# Power.net
KiCad netlist of a schematic drawn in Altium Designer
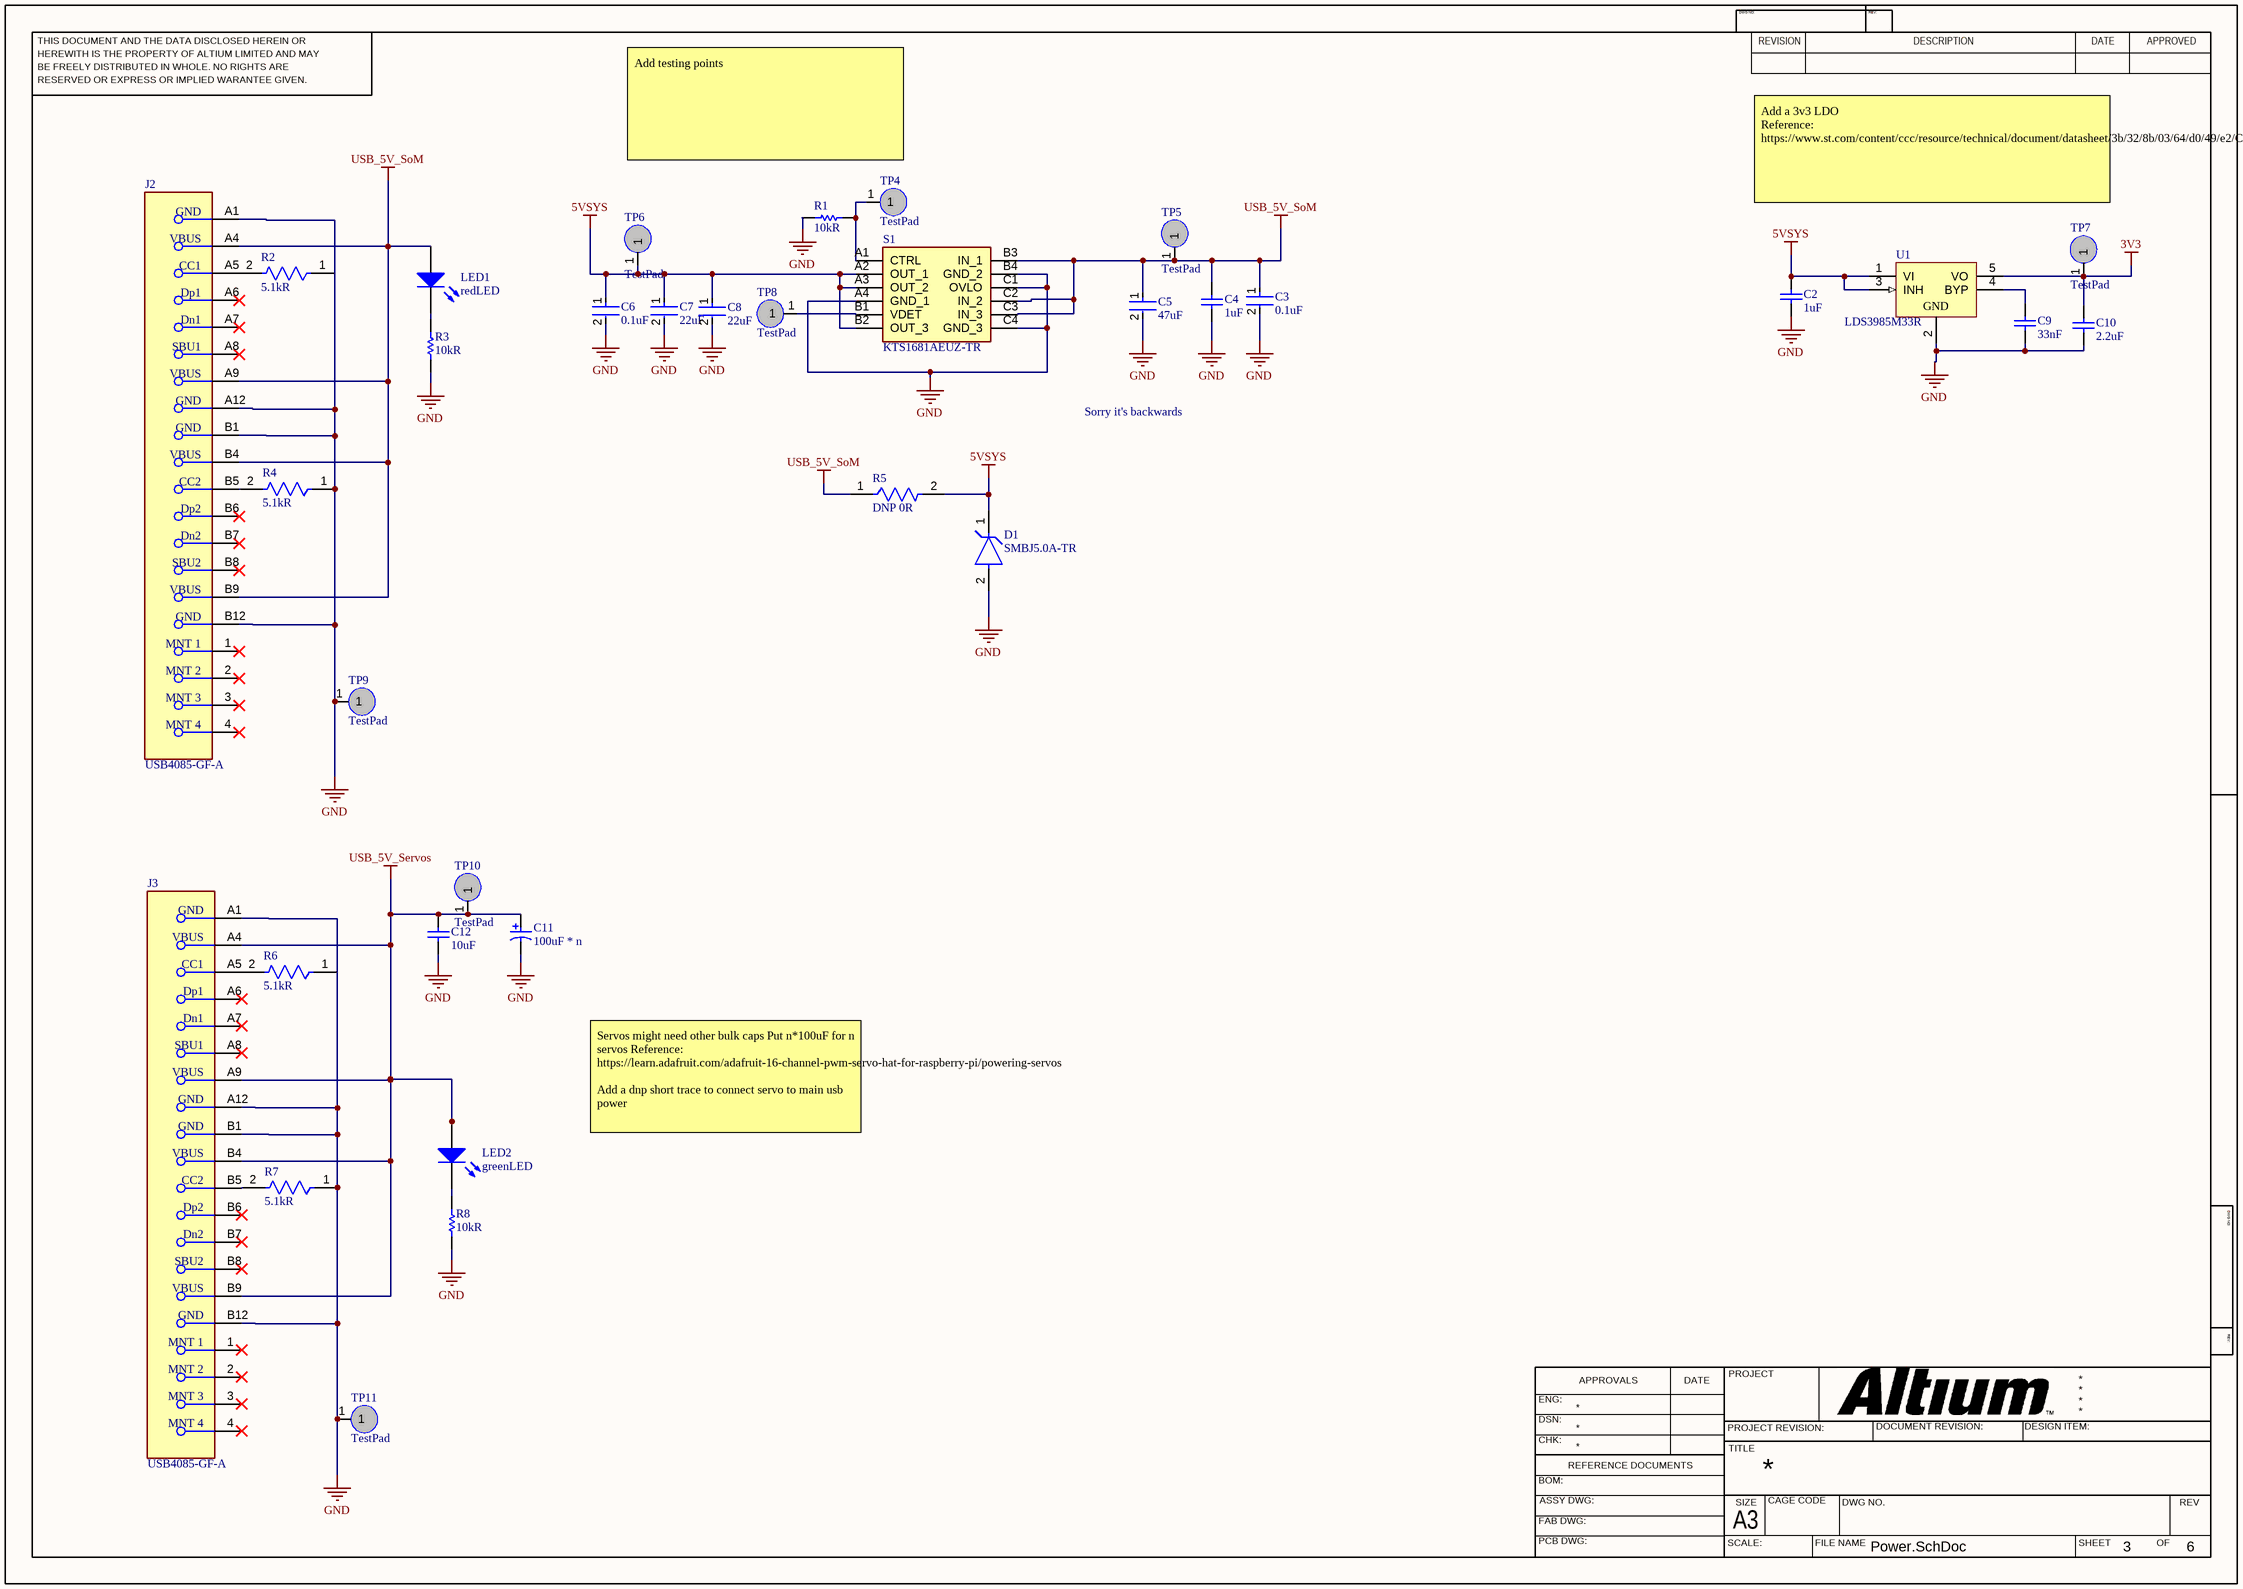
[diagram p0: Power.SchDoc]

(export (version "E")
  (design (tool "Eeschema 10.0.6"))
  (components
    (comp (ref "C2")
      (value "1uF")
      (footprint "CAPC2013X145X50LL20T25")
      (description "C0805C105K4PACTU")
      (fields (field (name "MANUFACTURER") "Kemet"))
      (libsource (lib "Altium Content Vault") (part "CAP"))
    )
    (comp (ref "C3")
      (value "0.1uF")
      (footprint "FP-C0603-CJ-MFG")
      (description "C0603X104K5RACTU CAP CER 0.1UF 50V X7R 0603")
      (fields (field (name "MANUFACTURER PART NUMBER") "C0603X104K5RACTU") (field (name "VOLTAGE") "50V"))
      (libsource (lib "Altium Content Vault") (part "11868f565c42a9108669ba33697ecf6"))
    )
    (comp (ref "C4")
      (value "1uF")
      (footprint "CAPC2013X145X50LL20T25")
      (description "C0805C105K4PACTU")
      (fields (field (name "MANUFACTURER") "Kemet"))
      (libsource (lib "Altium Content Vault") (part "CAP"))
    )
    (comp (ref "C5")
      (value "47uF")
      (footprint "FP-GRM31C-0_2-e0_3_0_8-IPC_C")
      (fields (field (name "TOLERANCE") "20%") (field (name "VOLTAGE") "6.3V"))
      (libsource (lib "Altium Content Vault") (part "02cd4be3c70576c341d710602a673aa"))
    )
    (comp (ref "C6")
      (value "0.1uF")
      (footprint "FP-C0603-CJ-MFG")
      (description "C0603X104K5RACTU CAP CER 0.1UF 50V X7R 0603")
      (fields (field (name "MANUFACTURER PART NUMBER") "C0603X104K5RACTU") (field (name "VOLTAGE") "50V"))
      (libsource (lib "Altium Content Vault") (part "11868f565c42a9108669ba33697ecf6"))
    )
    (comp (ref "C7")
      (value "22uF")
      (footprint "FP-GRM21B-0_15-MFG")
      (fields (field (name "VOLTAGE") "6.3V") (field (name "TOLERANCE") "20%"))
      (libsource (lib "Altium Content Vault") (part "b4654b650e69147ec39a6b967a45e02"))
    )
    (comp (ref "C8")
      (value "22uF")
      (footprint "FP-GRM21B-0_15-MFG")
      (fields (field (name "VOLTAGE") "6.3V") (field (name "TOLERANCE") "20%"))
      (libsource (lib "Altium Content Vault") (part "b4654b650e69147ec39a6b967a45e02"))
    )
    (comp (ref "C9")
      (value "33nF")
      (footprint "CAPC2013X94X50LL20T25")
      (description "08055C333JAT2A")
      (fields (field (name "MANUFACTURER") "AVX Interconnect / Elco"))
      (libsource (lib "Altium Content Vault") (part "CAP"))
    )
    (comp (ref "C10")
      (value "2.2uF")
      (footprint "CAPC2013X135X50ML10T20")
      (description "GRM21BR71C225KA12L")
      (fields (field (name "MANUFACTURER") "Murata"))
      (libsource (lib "Altium Content Vault") (part "CAP"))
    )
    (comp (ref "C11")
      (value "100uF * n")
      (footprint "CAPPR65-500-2000X1250X2200")
      (fields (field (name "MANUFACTURER") "Panasonic"))
      (libsource (lib "Altium Content Vault") (part "CAP-P-2"))
    )
    (comp (ref "C12")
      (value "10uF")
      (footprint "CAPC2013X145X20ML20")
      (fields
        (field (name "MANUFACTURER") "TDK")
        (field (name "TOLERANCE") "±10%")
        (field (name "PCN PART NUMBER") "MLCCPartNumberChange30/Nov/2012")
      )
      (libsource (lib "Altium Content Vault") (part "CAP-NP-2"))
    )
    (comp (ref "D1")
      (value "SMBJ5.0A-TR")
      (footprint "FP-SMB-MFG")
      (description "TVS DIODE 5V 13.4V SMB")
      (fields
        (field (name "MANUFACTURER") "STMicroelectronics")
        (field (name "OCTOPART") "https://octopart.com/smbj5.0a-tr-stmicroelectronics-347079")
      )
      (libsource (lib "Altium Content Vault") (part "7ddec9f632b8482e96f7745d0fbdf39"))
    )
    (comp (ref "J2")
      (value "USB4085-GF-A")
      (footprint "FP-USB4085-GF-A-MFG")
      (description "CONN RCPT USB2.0 TYPEC 16POS")
      (fields
        (field (name "MANUFACTURER") "Global Connector Technology")
        (field (name "OCTOPART") "https://octopart.com/usb4085-gf-a-global+connector+technology-94773699")
      )
      (libsource (lib "Altium Content Vault") (part "f6997dba88850a18107ac0013977506"))
    )
    (comp (ref "J3")
      (value "USB4085-GF-A")
      (footprint "FP-USB4085-GF-A-MFG")
      (description "CONN RCPT USB2.0 TYPEC 16POS")
      (fields
        (field (name "MANUFACTURER") "Global Connector Technology")
        (field (name "OCTOPART") "https://octopart.com/usb4085-gf-a-global+connector+technology-94773699")
      )
      (libsource (lib "Altium Content Vault") (part "f6997dba88850a18107ac0013977506"))
    )
    (comp (ref "LED1")
      (value "redLED")
      (footprint "0805_A")
      (description "SMD mono-color Chip LED, WL-SMCW, Super Red")
      (fields (field (name "MANUFACTURER") "Wuerth Elektronik") (field (name "PARTNUMBER") "150080SS75000"))
      (libsource (lib "Altium Content Vault") (part "WE-LED_K1A2-2"))
    )
    (comp (ref "LED2")
      (value "greenLED")
      (footprint "0805_A")
      (description "SMD mono-color Chip LED, WL-SMCW, Green")
      (fields (field (name "PARTNUMBER") "150080GS75000") (field (name "MANUFACTURER") "Wuerth Elektronik"))
      (libsource (lib "Altium Content Vault") (part "WE-LED_K1A2-2"))
    )
    (comp (ref "R1")
      (value "10kR")
      (footprint "RESC2013X60X35NL10T20")
      (fields (field (name "MANUFACTURER") "Yageo"))
      (libsource (lib "Altium Content Vault") (part "RES-2"))
    )
    (comp (ref "R2")
      (value "5.1kR")
      (footprint "FP-CRCW0805-e3-MFG")
      (description "RES Thick Film, 5.1kΩ, 1%, 0.125W, 100ppm/°C, 0805 CRCW08055K10FKEA")
      (fields (field (name "TOLERANCE") "1%"))
      (libsource (lib "Altium Content Vault") (part "1029c3af85768c4190bb7ad29bc67b5"))
    )
    (comp (ref "R3")
      (value "10kR")
      (footprint "RESC2013X60X35ML10T20")
      (fields (field (name "TOLERANCE") "1%") (field (name "MANUFACTURER") "Yageo"))
      (libsource (lib "Altium Content Vault") (part "RES-2"))
    )
    (comp (ref "R4")
      (value "5.1kR")
      (footprint "FP-CRCW0805-e3-MFG")
      (description "RES Thick Film, 5.1kΩ, 1%, 0.125W, 100ppm/°C, 0805 CRCW08055K10FKEA")
      (fields (field (name "TOLERANCE") "1%"))
      (libsource (lib "Altium Content Vault") (part "1029c3af85768c4190bb7ad29bc67b5"))
    )
    (comp (ref "R5")
      (value "DNP 0R")
      (footprint "FP-RC1206-MFG")
      (description "RC1206JR-070RL RES SMD 0 OHM JUMPER 1/4W 1206")
      (fields
        (field (name "MANUFACTURER PART NUMBER") "RC1206JR-070RL")
        (field (name "MANUFACTURER") "YAGEO")
      )
      (libsource (lib "Altium Content Vault") (part "1029c3af85768c4190bb7ad29bc67b5"))
    )
    (comp (ref "R6")
      (value "5.1kR")
      (footprint "FP-CRCW0805-e3-MFG")
      (description "RES Thick Film, 5.1kΩ, 1%, 0.125W, 100ppm/°C, 0805 CRCW08055K10FKEA")
      (fields (field (name "TOLERANCE") "1%"))
      (libsource (lib "Altium Content Vault") (part "1029c3af85768c4190bb7ad29bc67b5"))
    )
    (comp (ref "R7")
      (value "5.1kR")
      (footprint "FP-CRCW0805-e3-MFG")
      (description "RES Thick Film, 5.1kΩ, 1%, 0.125W, 100ppm/°C, 0805 CRCW08055K10FKEA")
      (fields (field (name "TOLERANCE") "1%"))
      (libsource (lib "Altium Content Vault") (part "1029c3af85768c4190bb7ad29bc67b5"))
    )
    (comp (ref "R8")
      (value "10kR")
      (footprint "RESC2013X60X35ML10T20")
      (fields (field (name "TOLERANCE") "1%") (field (name "MANUFACTURER") "Yageo"))
      (libsource (lib "Altium Content Vault") (part "RES-2"))
    )
    (comp (ref "S1")
      (value "KTS1681AEUZ-TR")
      (footprint "LayoutFootprintsGoogle:KTS1681AEUZTR")
      (description "Switch")
      (libsource (lib "*") (part "KTS1681AEUZ-TR"))
    )
    (comp (ref "TP4")
      (value "TestPad")
      (footprint "TestPad50mil")
      (libsource (lib "SchemSymbolsGoogle") (part "TestPad"))
    )
    (comp (ref "TP5")
      (value "TestPad")
      (footprint "TestPad50mil")
      (libsource (lib "SchemSymbolsGoogle") (part "TestPad"))
    )
    (comp (ref "TP6")
      (value "TestPad")
      (footprint "TestPad50mil")
      (libsource (lib "SchemSymbolsGoogle") (part "TestPad"))
    )
    (comp (ref "TP7")
      (value "TestPad")
      (footprint "TestPad50mil")
      (libsource (lib "SchemSymbolsGoogle") (part "TestPad"))
    )
    (comp (ref "TP8")
      (value "TestPad")
      (footprint "TestPad50mil")
      (libsource (lib "SchemSymbolsGoogle") (part "TestPad"))
    )
    (comp (ref "TP9")
      (value "TestPad")
      (footprint "TestPad50mil")
      (libsource (lib "SchemSymbolsGoogle") (part "TestPad"))
    )
    (comp (ref "TP10")
      (value "TestPad")
      (footprint "TestPad50mil")
      (libsource (lib "SchemSymbolsGoogle") (part "TestPad"))
    )
    (comp (ref "TP11")
      (value "TestPad")
      (footprint "TestPad50mil")
      (libsource (lib "SchemSymbolsGoogle") (part "TestPad"))
    )
    (comp (ref "U1")
      (value "LDS3985M33R")
      (footprint "SOT23-5L_M")
      (libsource (lib "Altium Content Vault") (part "PM-REG-LD3985-SOT5"))
    )
  )
  (nets
    (net (code "1") (name "3V3") (class "Default")
      (node (ref "C10") (pin "2") (pinfunction "2_2") (pintype "passive"))
      (node (ref "TP7") (pin "1") (pinfunction "1_1") (pintype "passive"))
      (node (ref "U1") (pin "5") (pinfunction "VO_5") (pintype "power_in"))
    )
    (net (code "2") (name "5VSYS") (class "Default")
      (node (ref "C2") (pin "2") (pinfunction "2_2") (pintype "passive"))
      (node (ref "C6") (pin "1") (pinfunction "1_1") (pintype "passive"))
      (node (ref "C7") (pin "1") (pinfunction "1_1") (pintype "passive"))
      (node (ref "C8") (pin "1") (pinfunction "1_1") (pintype "passive"))
      (node (ref "D1") (pin "1") (pinfunction "K_1") (pintype "passive"))
      (node (ref "R5") (pin "2") (pinfunction "2_2") (pintype "passive"))
      (node (ref "S1") (pin "A2") (pinfunction "OUT_1_A2") (pintype "passive"))
      (node (ref "S1") (pin "A3") (pinfunction "OUT_2_A3") (pintype "passive"))
      (node (ref "S1") (pin "B2") (pinfunction "OUT_3_B2") (pintype "passive"))
      (node (ref "TP6") (pin "1") (pinfunction "1_1") (pintype "passive"))
      (node (ref "U1") (pin "1") (pinfunction "VI_1") (pintype "power_in"))
      (node (ref "U1") (pin "3") (pinfunction "INH_3") (pintype "input"))
    )
    (net (code "3") (name "GND") (class "Default")
      (node (ref "C10") (pin "1") (pinfunction "1_1") (pintype "passive"))
      (node (ref "C11") (pin "2") (pinfunction "2_2") (pintype "passive"))
      (node (ref "C12") (pin "1") (pinfunction "1_1") (pintype "passive"))
      (node (ref "C2") (pin "1") (pinfunction "1_1") (pintype "passive"))
      (node (ref "C3") (pin "2") (pinfunction "2_2") (pintype "passive"))
      (node (ref "C4") (pin "1") (pinfunction "1_1") (pintype "passive"))
      (node (ref "C5") (pin "2") (pinfunction "2_2") (pintype "passive"))
      (node (ref "C6") (pin "2") (pinfunction "2_2") (pintype "passive"))
      (node (ref "C7") (pin "2") (pinfunction "2_2") (pintype "passive"))
      (node (ref "C8") (pin "2") (pinfunction "2_2") (pintype "passive"))
      (node (ref "C9") (pin "1") (pinfunction "1_1") (pintype "passive"))
      (node (ref "D1") (pin "2") (pinfunction "A_2") (pintype "passive"))
      (node (ref "J2") (pin "A1") (pinfunction "GND_A1") (pintype "power_in"))
      (node (ref "J2") (pin "A12") (pinfunction "GND_A12") (pintype "power_in"))
      (node (ref "J2") (pin "B1") (pinfunction "GND_B1") (pintype "power_in"))
      (node (ref "J2") (pin "B12") (pinfunction "GND_B12") (pintype "power_in"))
      (node (ref "J3") (pin "A1") (pinfunction "GND_A1") (pintype "power_in"))
      (node (ref "J3") (pin "A12") (pinfunction "GND_A12") (pintype "power_in"))
      (node (ref "J3") (pin "B1") (pinfunction "GND_B1") (pintype "power_in"))
      (node (ref "J3") (pin "B12") (pinfunction "GND_B12") (pintype "power_in"))
      (node (ref "R1") (pin "2") (pinfunction "2_2") (pintype "passive"))
      (node (ref "R3") (pin "1") (pinfunction "1_1") (pintype "passive"))
      (node (ref "R4") (pin "1") (pinfunction "1_1") (pintype "passive"))
      (node (ref "R7") (pin "1") (pinfunction "1_1") (pintype "passive"))
      (node (ref "R8") (pin "1") (pinfunction "1_1") (pintype "passive"))
      (node (ref "S1") (pin "A4") (pinfunction "GND_1_A4") (pintype "passive"))
      (node (ref "S1") (pin "B4") (pinfunction "GND_2_B4") (pintype "passive"))
      (node (ref "S1") (pin "C1") (pinfunction "OVLO_C1") (pintype "passive"))
      (node (ref "S1") (pin "C4") (pinfunction "GND_3_C4") (pintype "passive"))
      (node (ref "TP11") (pin "1") (pinfunction "1_1") (pintype "passive"))
      (node (ref "TP9") (pin "1") (pinfunction "1_1") (pintype "passive"))
      (node (ref "U1") (pin "2") (pinfunction "GND_2") (pintype "power_in"))
    )
    (net (code "4") (name "Net-(J2-CC1)") (class "Default")
      (node (ref "J2") (pin "A5") (pinfunction "CC1_A5") (pintype "passive"))
      (node (ref "R2") (pin "2") (pinfunction "2_2") (pintype "passive"))
    )
    (net (code "5") (name "Net-(J2-CC2)") (class "Default")
      (node (ref "J2") (pin "B5") (pinfunction "CC2_B5") (pintype "passive"))
      (node (ref "R4") (pin "2") (pinfunction "2_2") (pintype "passive"))
    )
    (net (code "6") (name "Net-(J3-CC1)") (class "Default")
      (node (ref "J3") (pin "A5") (pinfunction "CC1_A5") (pintype "passive"))
      (node (ref "R6") (pin "2") (pinfunction "2_2") (pintype "passive"))
    )
    (net (code "7") (name "Net-(J3-CC2)") (class "Default")
      (node (ref "J3") (pin "B5") (pinfunction "CC2_B5") (pintype "passive"))
      (node (ref "R7") (pin "2") (pinfunction "2_2") (pintype "passive"))
    )
    (net (code "8") (name "Net-(LED1-K)") (class "Default")
      (node (ref "LED1") (pin "1") (pinfunction "K_1") (pintype "passive"))
      (node (ref "R3") (pin "2") (pinfunction "2_2") (pintype "passive"))
    )
    (net (code "9") (name "Net-(LED2-K)") (class "Default")
      (node (ref "LED2") (pin "1") (pinfunction "K_1") (pintype "passive"))
      (node (ref "R8") (pin "2") (pinfunction "2_2") (pintype "passive"))
    )
    (net (code "10") (name "Net-(S1-CTRL)") (class "Default")
      (node (ref "R1") (pin "1") (pinfunction "1_1") (pintype "passive"))
      (node (ref "S1") (pin "A1") (pinfunction "CTRL_A1") (pintype "passive"))
      (node (ref "TP4") (pin "1") (pinfunction "1_1") (pintype "passive"))
    )
    (net (code "11") (name "Net-(S1-VDET)") (class "Default")
      (node (ref "S1") (pin "B1") (pinfunction "VDET_B1") (pintype "passive"))
      (node (ref "TP8") (pin "1") (pinfunction "1_1") (pintype "passive"))
    )
    (net (code "12") (name "Net-(U1-BYP)") (class "Default")
      (node (ref "C9") (pin "2") (pinfunction "2_2") (pintype "passive"))
      (node (ref "U1") (pin "4") (pinfunction "BYP_4") (pintype "passive"))
    )
    (net (code "13") (name "USB_5V_Servos") (class "Default")
      (node (ref "C11") (pin "1") (pinfunction "1_1") (pintype "passive"))
      (node (ref "C12") (pin "2") (pinfunction "2_2") (pintype "passive"))
      (node (ref "J3") (pin "A4") (pinfunction "VBUS_A4") (pintype "power_in"))
      (node (ref "J3") (pin "A9") (pinfunction "VBUS_A9") (pintype "power_in"))
      (node (ref "J3") (pin "B4") (pinfunction "VBUS_B4") (pintype "power_in"))
      (node (ref "J3") (pin "B9") (pinfunction "VBUS_B9") (pintype "power_in"))
      (node (ref "LED2") (pin "2") (pinfunction "A_2") (pintype "passive"))
      (node (ref "TP10") (pin "1") (pinfunction "1_1") (pintype "passive"))
    )
    (net (code "14") (name "USB_5V_SoM") (class "Default")
      (node (ref "C3") (pin "1") (pinfunction "1_1") (pintype "passive"))
      (node (ref "C4") (pin "2") (pinfunction "2_2") (pintype "passive"))
      (node (ref "C5") (pin "1") (pinfunction "1_1") (pintype "passive"))
      (node (ref "J2") (pin "A4") (pinfunction "VBUS_A4") (pintype "power_in"))
      (node (ref "J2") (pin "A9") (pinfunction "VBUS_A9") (pintype "power_in"))
      (node (ref "J2") (pin "B4") (pinfunction "VBUS_B4") (pintype "power_in"))
      (node (ref "J2") (pin "B9") (pinfunction "VBUS_B9") (pintype "power_in"))
      (node (ref "LED1") (pin "2") (pinfunction "A_2") (pintype "passive"))
      (node (ref "R5") (pin "1") (pinfunction "1_1") (pintype "passive"))
      (node (ref "S1") (pin "B3") (pinfunction "IN_1_B3") (pintype "passive"))
      (node (ref "S1") (pin "C2") (pinfunction "IN_2_C2") (pintype "passive"))
      (node (ref "S1") (pin "C3") (pinfunction "IN_3_C3") (pintype "passive"))
      (node (ref "TP5") (pin "1") (pinfunction "1_1") (pintype "passive"))
    )
    (net (code "15") (name "unconnected-(J2-Dn1-PadA7)") (class "Default")
      (node (ref "J2") (pin "A7") (pinfunction "Dn1_A7") (pintype "passive+no_connect"))
    )
    (net (code "16") (name "unconnected-(J2-Dn2-PadB7)") (class "Default")
      (node (ref "J2") (pin "B7") (pinfunction "Dn2_B7") (pintype "passive+no_connect"))
    )
    (net (code "17") (name "unconnected-(J2-Dp1-PadA6)") (class "Default")
      (node (ref "J2") (pin "A6") (pinfunction "Dp1_A6") (pintype "passive+no_connect"))
    )
    (net (code "18") (name "unconnected-(J2-Dp2-PadB6)") (class "Default")
      (node (ref "J2") (pin "B6") (pinfunction "Dp2_B6") (pintype "passive+no_connect"))
    )
    (net (code "19") (name "unconnected-(J2-MNT_1-Pad1)") (class "Default")
      (node (ref "J2") (pin "1") (pinfunction "MNT_1_1") (pintype "passive+no_connect"))
    )
    (net (code "20") (name "unconnected-(J2-MNT_2-Pad2)") (class "Default")
      (node (ref "J2") (pin "2") (pinfunction "MNT_2_2") (pintype "passive+no_connect"))
    )
    (net (code "21") (name "unconnected-(J2-MNT_3-Pad3)") (class "Default")
      (node (ref "J2") (pin "3") (pinfunction "MNT_3_3") (pintype "passive+no_connect"))
    )
    (net (code "22") (name "unconnected-(J2-MNT_4-Pad4)") (class "Default")
      (node (ref "J2") (pin "4") (pinfunction "MNT_4_4") (pintype "passive+no_connect"))
    )
    (net (code "23") (name "unconnected-(J2-SBU1-PadA8)") (class "Default")
      (node (ref "J2") (pin "A8") (pinfunction "SBU1_A8") (pintype "passive+no_connect"))
    )
    (net (code "24") (name "unconnected-(J2-SBU2-PadB8)") (class "Default")
      (node (ref "J2") (pin "B8") (pinfunction "SBU2_B8") (pintype "passive+no_connect"))
    )
    (net (code "25") (name "unconnected-(J3-Dn1-PadA7)") (class "Default")
      (node (ref "J3") (pin "A7") (pinfunction "Dn1_A7") (pintype "passive+no_connect"))
    )
    (net (code "26") (name "unconnected-(J3-Dn2-PadB7)") (class "Default")
      (node (ref "J3") (pin "B7") (pinfunction "Dn2_B7") (pintype "passive+no_connect"))
    )
    (net (code "27") (name "unconnected-(J3-Dp1-PadA6)") (class "Default")
      (node (ref "J3") (pin "A6") (pinfunction "Dp1_A6") (pintype "passive+no_connect"))
    )
    (net (code "28") (name "unconnected-(J3-Dp2-PadB6)") (class "Default")
      (node (ref "J3") (pin "B6") (pinfunction "Dp2_B6") (pintype "passive+no_connect"))
    )
    (net (code "29") (name "unconnected-(J3-MNT_1-Pad1)") (class "Default")
      (node (ref "J3") (pin "1") (pinfunction "MNT_1_1") (pintype "passive+no_connect"))
    )
    (net (code "30") (name "unconnected-(J3-MNT_2-Pad2)") (class "Default")
      (node (ref "J3") (pin "2") (pinfunction "MNT_2_2") (pintype "passive+no_connect"))
    )
    (net (code "31") (name "unconnected-(J3-MNT_3-Pad3)") (class "Default")
      (node (ref "J3") (pin "3") (pinfunction "MNT_3_3") (pintype "passive+no_connect"))
    )
    (net (code "32") (name "unconnected-(J3-MNT_4-Pad4)") (class "Default")
      (node (ref "J3") (pin "4") (pinfunction "MNT_4_4") (pintype "passive+no_connect"))
    )
    (net (code "33") (name "unconnected-(J3-SBU1-PadA8)") (class "Default")
      (node (ref "J3") (pin "A8") (pinfunction "SBU1_A8") (pintype "passive+no_connect"))
    )
    (net (code "34") (name "unconnected-(J3-SBU2-PadB8)") (class "Default")
      (node (ref "J3") (pin "B8") (pinfunction "SBU2_B8") (pintype "passive+no_connect"))
    )
    (net (code "35") (name "unconnected-(R2-Pad1)") (class "Default")
      (node (ref "R2") (pin "1") (pinfunction "1_1") (pintype "passive"))
    )
    (net (code "36") (name "unconnected-(R6-Pad1)") (class "Default")
      (node (ref "R6") (pin "1") (pinfunction "1_1") (pintype "passive"))
    )
  )
)
